# vga-switch.net
KiCad netlist of a schematic drawn in EAGLE
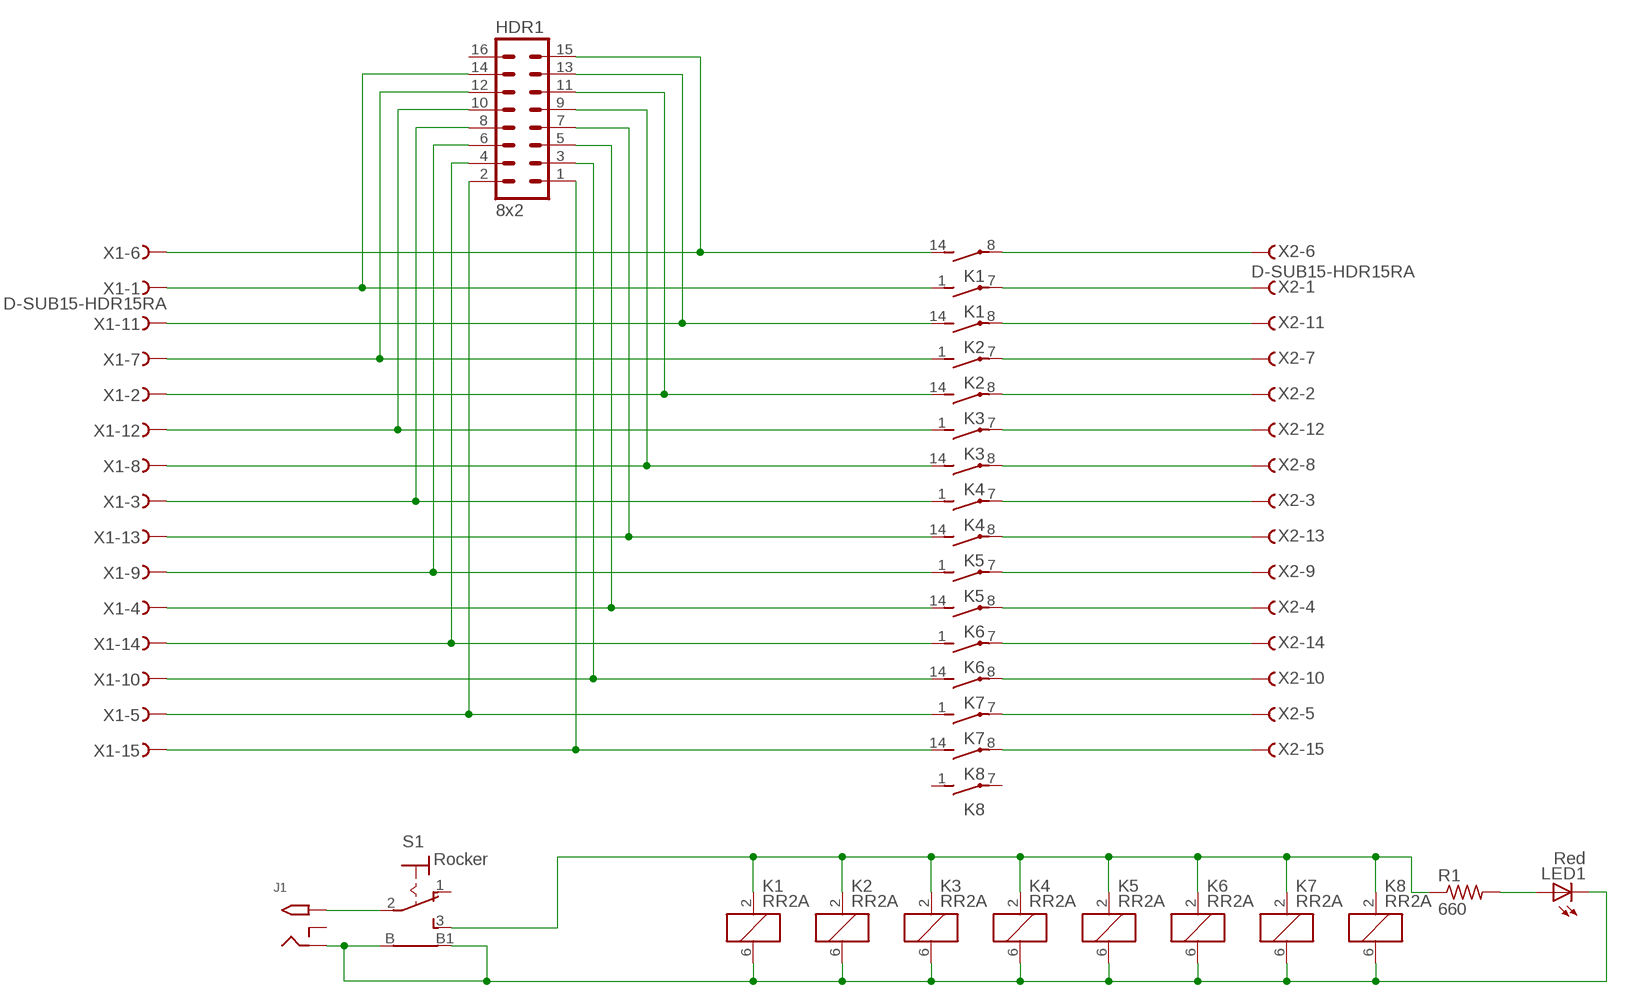
[diagram p0: schematic, sheet 1]

(export (version "E")
  (design (tool "Eeschema 10.0.6"))
  (components
    (comp (ref "HDR1")
      (value "8x2")
      (footprint "eagle-import:MA08-2")
      (libsource (lib "eagle-import") (part "MA08-2"))
    )
    (comp (ref "J1")
      (value "2.1MMJACKTHM")
      (footprint "eagle-import:PJ-102A")
      (libsource (lib "eagle-import") (part "2.1MMJACKTHM"))
    )
    (comp (ref "K1")
      (value "RR2A")
      (footprint "eagle-import:RR2A")
      (libsource (lib "eagle-import") (part "RR2A"))
    )
    (comp (ref "K2")
      (value "RR2A")
      (footprint "eagle-import:RR2A")
      (libsource (lib "eagle-import") (part "RR2A"))
    )
    (comp (ref "K3")
      (value "RR2A")
      (footprint "eagle-import:RR2A")
      (libsource (lib "eagle-import") (part "RR2A"))
    )
    (comp (ref "K4")
      (value "RR2A")
      (footprint "eagle-import:RR2A")
      (libsource (lib "eagle-import") (part "RR2A"))
    )
    (comp (ref "K5")
      (value "RR2A")
      (footprint "eagle-import:RR2A")
      (libsource (lib "eagle-import") (part "RR2A"))
    )
    (comp (ref "K6")
      (value "RR2A")
      (footprint "eagle-import:RR2A")
      (libsource (lib "eagle-import") (part "RR2A"))
    )
    (comp (ref "K7")
      (value "RR2A")
      (footprint "eagle-import:RR2A")
      (libsource (lib "eagle-import") (part "RR2A"))
    )
    (comp (ref "K8")
      (value "RR2A")
      (footprint "eagle-import:RR2A")
      (libsource (lib "eagle-import") (part "RR2A"))
    )
    (comp (ref "LED1")
      (value "Red")
      (footprint "eagle-import:LED5MM")
      (libsource (lib "eagle-import") (part "LED5MM"))
    )
    (comp (ref "R1")
      (value "660")
      (footprint "eagle-import:0207_10")
      (libsource (lib "eagle-import") (part "R-US_0207/10"))
    )
    (comp (ref "S1")
      (value "Rocker")
      (footprint "eagle-import:ROCKERSWITCH")
      (libsource (lib "eagle-import") (part "ROCKERSWITCH"))
    )
    (comp (ref "X1")
      (value "D-SUB15-HDR15RA")
      (footprint "eagle-import:HDR15RA")
      (libsource (lib "eagle-import") (part "D-SUB15-HDR15RA"))
    )
    (comp (ref "X2")
      (value "D-SUB15-HDR15RA")
      (footprint "eagle-import:HDR15RA")
      (libsource (lib "eagle-import") (part "D-SUB15-HDR15RA"))
    )
  )
  (nets
    (net (code "1") (name "Net-(K1A-1)") (class "Default")
      (node (ref "K1") (pin "2") (pinfunction "1_2") (pintype "passive"))
      (node (ref "K2") (pin "2") (pinfunction "1_2") (pintype "passive"))
      (node (ref "K3") (pin "2") (pinfunction "1_2") (pintype "passive"))
      (node (ref "K4") (pin "2") (pinfunction "1_2") (pintype "passive"))
      (node (ref "K5") (pin "2") (pinfunction "1_2") (pintype "passive"))
      (node (ref "K6") (pin "2") (pinfunction "1_2") (pintype "passive"))
      (node (ref "K7") (pin "2") (pinfunction "1_2") (pintype "passive"))
      (node (ref "K8") (pin "2") (pinfunction "1_2") (pintype "passive"))
      (node (ref "R1") (pin "1") (pinfunction "1_1") (pintype "passive"))
      (node (ref "S1") (pin "3") (pinfunction "S_3") (pintype "passive"))
    )
    (net (code "2") (name "Net-(K1A-2)") (class "Default")
      (node (ref "J1") (pin "RING") (pinfunction "RING_RING") (pintype "bidirectional"))
      (node (ref "K1") (pin "6") (pinfunction "2_6") (pintype "passive"))
      (node (ref "K2") (pin "6") (pinfunction "2_6") (pintype "passive"))
      (node (ref "K3") (pin "6") (pinfunction "2_6") (pintype "passive"))
      (node (ref "K4") (pin "6") (pinfunction "2_6") (pintype "passive"))
      (node (ref "K5") (pin "6") (pinfunction "2_6") (pintype "passive"))
      (node (ref "K6") (pin "6") (pinfunction "2_6") (pintype "passive"))
      (node (ref "K7") (pin "6") (pinfunction "2_6") (pintype "passive"))
      (node (ref "K8") (pin "6") (pinfunction "2_6") (pintype "passive"))
      (node (ref "LED1") (pin "K") (pinfunction "C_K") (pintype "passive"))
      (node (ref "S1") (pin "B") (pinfunction "B_B") (pintype "passive"))
      (node (ref "S1") (pin "B1") (pinfunction "B1_B1") (pintype "passive"))
    )
    (net (code "3") (name "Net-(K1B-P)") (class "Default")
      (node (ref "K1") (pin "7") (pinfunction "P_7") (pintype "passive"))
      (node (ref "X2") (pin "1") (pinfunction "F_1") (pintype "passive"))
    )
    (net (code "4") (name "Net-(K1B-S)") (class "Default")
      (node (ref "HDR1") (pin "14") (pinfunction "14_14") (pintype "passive"))
      (node (ref "K1") (pin "1") (pinfunction "S_1") (pintype "passive"))
      (node (ref "X1") (pin "1") (pinfunction "F_1") (pintype "passive"))
    )
    (net (code "5") (name "Net-(K1C-P)") (class "Default")
      (node (ref "K1") (pin "8") (pinfunction "P_8") (pintype "passive"))
      (node (ref "X2") (pin "6") (pinfunction "F_6") (pintype "passive"))
    )
    (net (code "6") (name "Net-(K1C-S)") (class "Default")
      (node (ref "HDR1") (pin "15") (pinfunction "15_15") (pintype "passive"))
      (node (ref "K1") (pin "14") (pinfunction "S_14") (pintype "passive"))
      (node (ref "X1") (pin "6") (pinfunction "F_6") (pintype "passive"))
    )
    (net (code "7") (name "Net-(K2B-P)") (class "Default")
      (node (ref "K2") (pin "7") (pinfunction "P_7") (pintype "passive"))
      (node (ref "X2") (pin "7") (pinfunction "F_7") (pintype "passive"))
    )
    (net (code "8") (name "Net-(K2B-S)") (class "Default")
      (node (ref "HDR1") (pin "12") (pinfunction "12_12") (pintype "passive"))
      (node (ref "K2") (pin "1") (pinfunction "S_1") (pintype "passive"))
      (node (ref "X1") (pin "7") (pinfunction "F_7") (pintype "passive"))
    )
    (net (code "9") (name "Net-(K2C-P)") (class "Default")
      (node (ref "K2") (pin "8") (pinfunction "P_8") (pintype "passive"))
      (node (ref "X2") (pin "11") (pinfunction "F_11") (pintype "passive"))
    )
    (net (code "10") (name "Net-(K2C-S)") (class "Default")
      (node (ref "HDR1") (pin "13") (pinfunction "13_13") (pintype "passive"))
      (node (ref "K2") (pin "14") (pinfunction "S_14") (pintype "passive"))
      (node (ref "X1") (pin "11") (pinfunction "F_11") (pintype "passive"))
    )
    (net (code "11") (name "Net-(K3B-P)") (class "Default")
      (node (ref "K3") (pin "7") (pinfunction "P_7") (pintype "passive"))
      (node (ref "X2") (pin "12") (pinfunction "F_12") (pintype "passive"))
    )
    (net (code "12") (name "Net-(K3B-S)") (class "Default")
      (node (ref "HDR1") (pin "10") (pinfunction "10_10") (pintype "passive"))
      (node (ref "K3") (pin "1") (pinfunction "S_1") (pintype "passive"))
      (node (ref "X1") (pin "12") (pinfunction "F_12") (pintype "passive"))
    )
    (net (code "13") (name "Net-(K3C-P)") (class "Default")
      (node (ref "K3") (pin "8") (pinfunction "P_8") (pintype "passive"))
      (node (ref "X2") (pin "2") (pinfunction "F_2") (pintype "passive"))
    )
    (net (code "14") (name "Net-(K3C-S)") (class "Default")
      (node (ref "HDR1") (pin "11") (pinfunction "11_11") (pintype "passive"))
      (node (ref "K3") (pin "14") (pinfunction "S_14") (pintype "passive"))
      (node (ref "X1") (pin "2") (pinfunction "F_2") (pintype "passive"))
    )
    (net (code "15") (name "Net-(K4B-P)") (class "Default")
      (node (ref "K4") (pin "7") (pinfunction "P_7") (pintype "passive"))
      (node (ref "X2") (pin "3") (pinfunction "F_3") (pintype "passive"))
    )
    (net (code "16") (name "Net-(K4B-S)") (class "Default")
      (node (ref "HDR1") (pin "8") (pinfunction "8_8") (pintype "passive"))
      (node (ref "K4") (pin "1") (pinfunction "S_1") (pintype "passive"))
      (node (ref "X1") (pin "3") (pinfunction "F_3") (pintype "passive"))
    )
    (net (code "17") (name "Net-(K4C-P)") (class "Default")
      (node (ref "K4") (pin "8") (pinfunction "P_8") (pintype "passive"))
      (node (ref "X2") (pin "8") (pinfunction "F_8") (pintype "passive"))
    )
    (net (code "18") (name "Net-(K4C-S)") (class "Default")
      (node (ref "HDR1") (pin "9") (pinfunction "9_9") (pintype "passive"))
      (node (ref "K4") (pin "14") (pinfunction "S_14") (pintype "passive"))
      (node (ref "X1") (pin "8") (pinfunction "F_8") (pintype "passive"))
    )
    (net (code "19") (name "Net-(K5B-P)") (class "Default")
      (node (ref "K5") (pin "7") (pinfunction "P_7") (pintype "passive"))
      (node (ref "X2") (pin "9") (pinfunction "F_9") (pintype "passive"))
    )
    (net (code "20") (name "Net-(K5B-S)") (class "Default")
      (node (ref "HDR1") (pin "6") (pinfunction "6_6") (pintype "passive"))
      (node (ref "K5") (pin "1") (pinfunction "S_1") (pintype "passive"))
      (node (ref "X1") (pin "9") (pinfunction "F_9") (pintype "passive"))
    )
    (net (code "21") (name "Net-(K5C-P)") (class "Default")
      (node (ref "K5") (pin "8") (pinfunction "P_8") (pintype "passive"))
      (node (ref "X2") (pin "13") (pinfunction "F_13") (pintype "passive"))
    )
    (net (code "22") (name "Net-(K5C-S)") (class "Default")
      (node (ref "HDR1") (pin "7") (pinfunction "7_7") (pintype "passive"))
      (node (ref "K5") (pin "14") (pinfunction "S_14") (pintype "passive"))
      (node (ref "X1") (pin "13") (pinfunction "F_13") (pintype "passive"))
    )
    (net (code "23") (name "Net-(K6B-P)") (class "Default")
      (node (ref "K6") (pin "7") (pinfunction "P_7") (pintype "passive"))
      (node (ref "X2") (pin "14") (pinfunction "F_14") (pintype "passive"))
    )
    (net (code "24") (name "Net-(K6B-S)") (class "Default")
      (node (ref "HDR1") (pin "4") (pinfunction "4_4") (pintype "passive"))
      (node (ref "K6") (pin "1") (pinfunction "S_1") (pintype "passive"))
      (node (ref "X1") (pin "14") (pinfunction "F_14") (pintype "passive"))
    )
    (net (code "25") (name "Net-(K6C-P)") (class "Default")
      (node (ref "K6") (pin "8") (pinfunction "P_8") (pintype "passive"))
      (node (ref "X2") (pin "4") (pinfunction "F_4") (pintype "passive"))
    )
    (net (code "26") (name "Net-(K6C-S)") (class "Default")
      (node (ref "HDR1") (pin "5") (pinfunction "5_5") (pintype "passive"))
      (node (ref "K6") (pin "14") (pinfunction "S_14") (pintype "passive"))
      (node (ref "X1") (pin "4") (pinfunction "F_4") (pintype "passive"))
    )
    (net (code "27") (name "Net-(K7B-P)") (class "Default")
      (node (ref "K7") (pin "7") (pinfunction "P_7") (pintype "passive"))
      (node (ref "X2") (pin "5") (pinfunction "F_5") (pintype "passive"))
    )
    (net (code "28") (name "Net-(K7B-S)") (class "Default")
      (node (ref "HDR1") (pin "2") (pinfunction "2_2") (pintype "passive"))
      (node (ref "K7") (pin "1") (pinfunction "S_1") (pintype "passive"))
      (node (ref "X1") (pin "5") (pinfunction "F_5") (pintype "passive"))
    )
    (net (code "29") (name "Net-(K7C-P)") (class "Default")
      (node (ref "K7") (pin "8") (pinfunction "P_8") (pintype "passive"))
      (node (ref "X2") (pin "10") (pinfunction "F_10") (pintype "passive"))
    )
    (net (code "30") (name "Net-(K7C-S)") (class "Default")
      (node (ref "HDR1") (pin "3") (pinfunction "3_3") (pintype "passive"))
      (node (ref "K7") (pin "14") (pinfunction "S_14") (pintype "passive"))
      (node (ref "X1") (pin "10") (pinfunction "F_10") (pintype "passive"))
    )
    (net (code "31") (name "Net-(K8C-P)") (class "Default")
      (node (ref "K8") (pin "8") (pinfunction "P_8") (pintype "passive"))
      (node (ref "X2") (pin "15") (pinfunction "F_15") (pintype "passive"))
    )
    (net (code "32") (name "Net-(K8C-S)") (class "Default")
      (node (ref "HDR1") (pin "1") (pinfunction "1_1") (pintype "passive"))
      (node (ref "K8") (pin "14") (pinfunction "S_14") (pintype "passive"))
      (node (ref "X1") (pin "15") (pinfunction "F_15") (pintype "passive"))
    )
    (net (code "33") (name "Net-(LED1-PadA)") (class "Default")
      (node (ref "LED1") (pin "A") (pinfunction "A_A") (pintype "passive"))
      (node (ref "R1") (pin "2") (pinfunction "2_2") (pintype "passive"))
    )
    (net (code "34") (name "Net-(S1-P)") (class "Default")
      (node (ref "J1") (pin "TIP") (pinfunction "TIP_TIP") (pintype "bidirectional"))
      (node (ref "S1") (pin "2") (pinfunction "P_2") (pintype "passive"))
    )
    (net (code "35") (name "unconnected-(HDR1-Pad16)") (class "Default")
      (node (ref "HDR1") (pin "16") (pinfunction "16_16") (pintype "passive"))
    )
    (net (code "36") (name "unconnected-(J1-PadRING_SW)") (class "Default")
      (node (ref "J1") (pin "RING_SW") (pinfunction "RING_SW_RING_SW") (pintype "bidirectional"))
    )
    (net (code "37") (name "unconnected-(K8B-P-Pad7)") (class "Default")
      (node (ref "K8") (pin "7") (pinfunction "P_7") (pintype "passive"))
    )
    (net (code "38") (name "unconnected-(K8B-S-Pad1)") (class "Default")
      (node (ref "K8") (pin "1") (pinfunction "S_1") (pintype "passive"))
    )
    (net (code "39") (name "unconnected-(S1-O-Pad1)") (class "Default")
      (node (ref "S1") (pin "1") (pinfunction "O_1") (pintype "passive"))
    )
  )
)
